# 1-Schematic_5G23new.net
KiCad netlist of a schematic drawn in EasyEDA
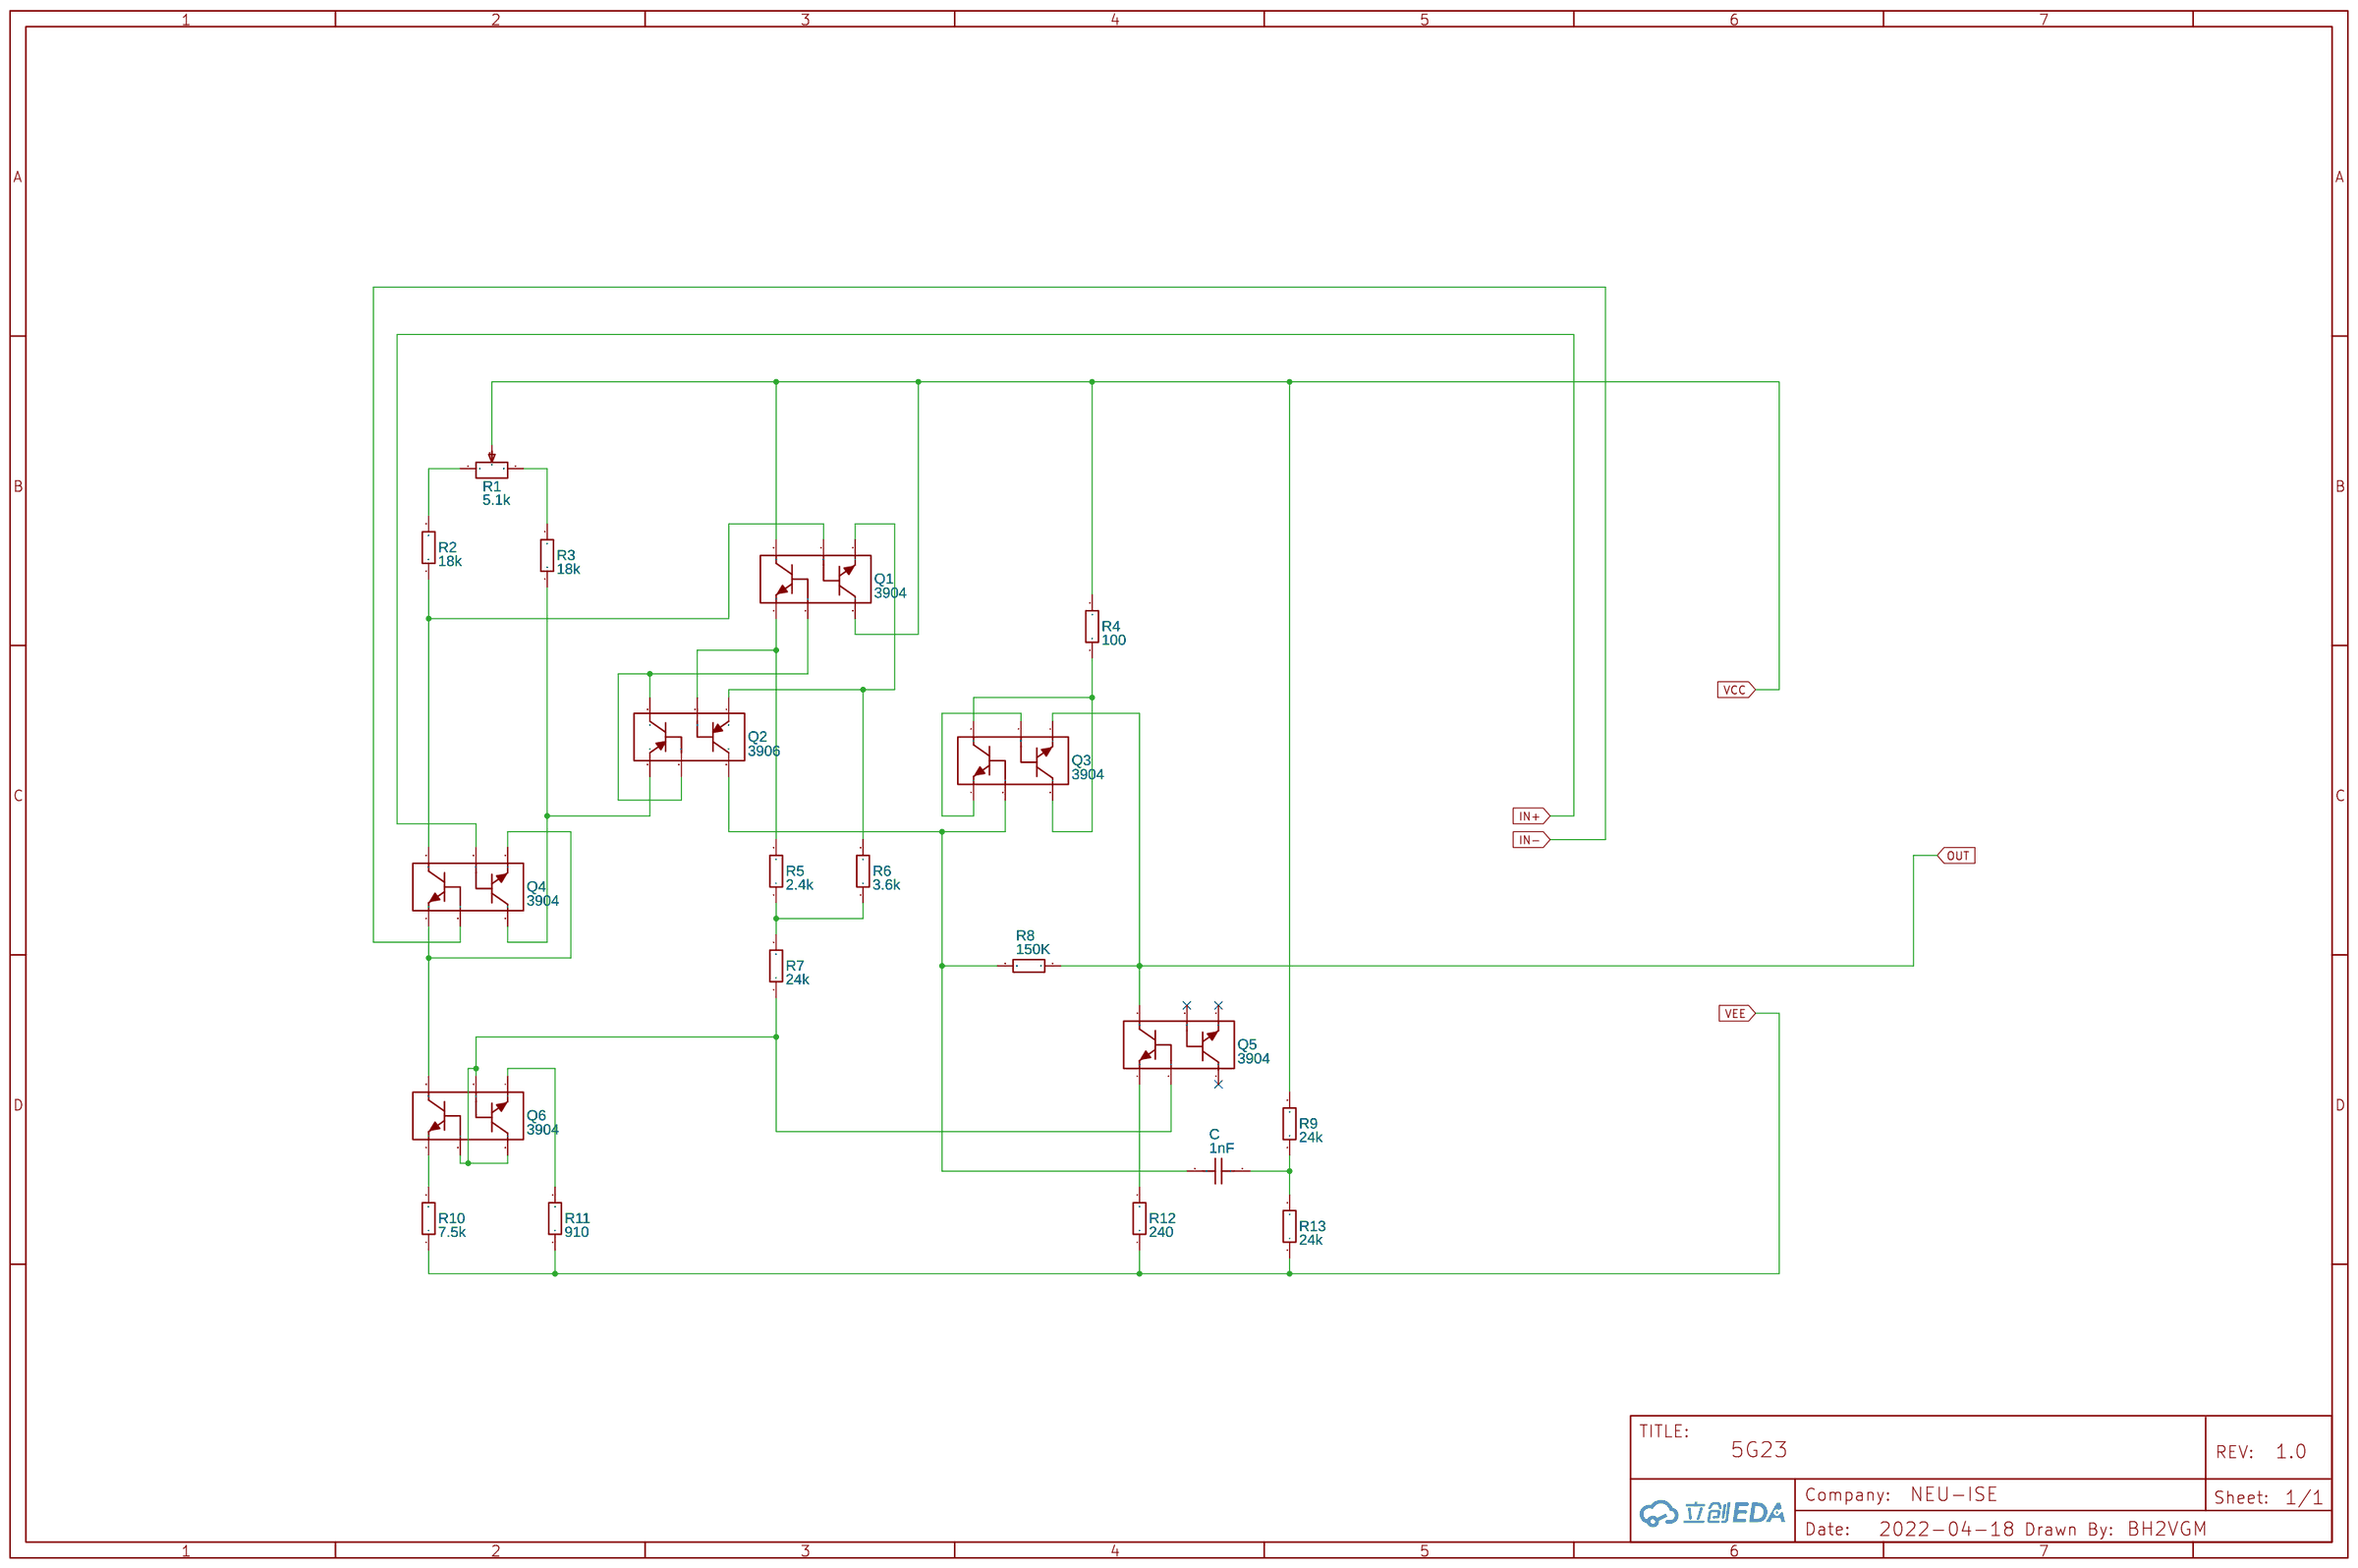
[diagram p0: 5G23]
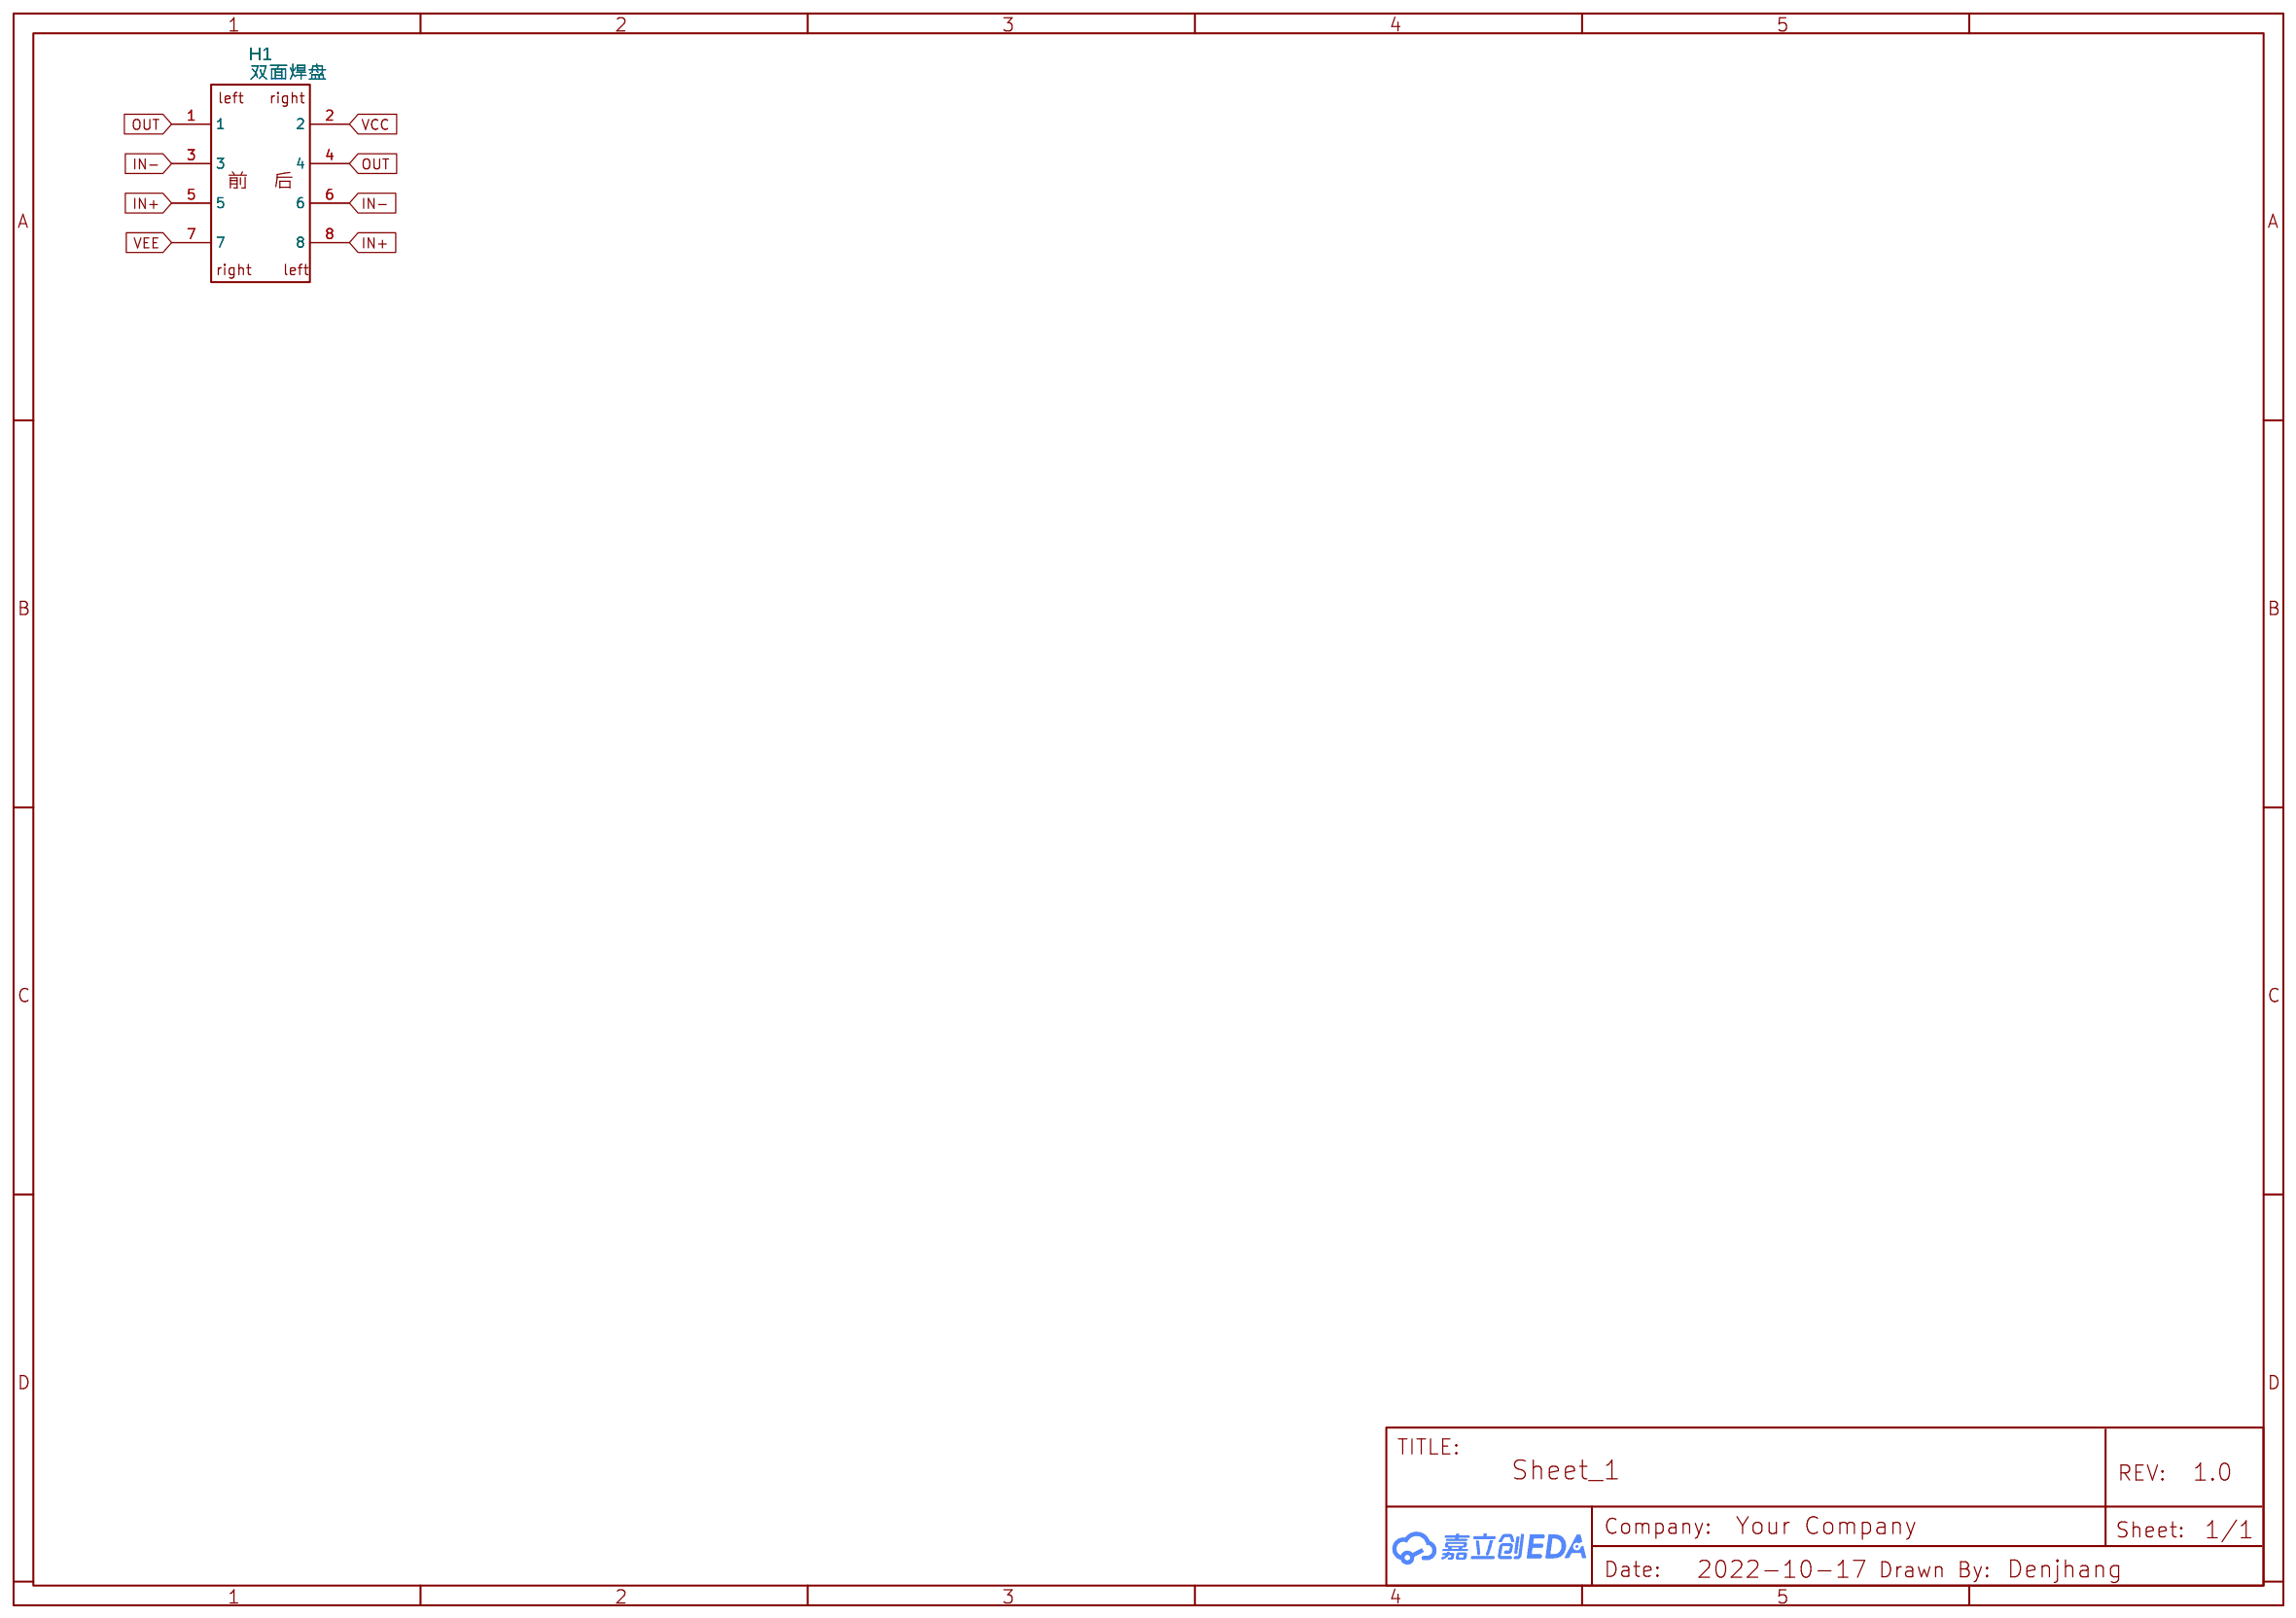
[diagram p1: CONN]

(export (version "E")
  (design (tool "Eeschema 10.0.6"))
  (components
    (comp (ref "C")
      (value "1nF")
      (fields
        (field (name "BOM_Manufacturer Part") "1nF-C0603")
        (field (name "BOM_Supplier Part") "C2940049")
      )
      (libsource (lib "") (part "1NF-C0603"))
    )
    (comp (ref "Q1")
      (value "3904")
      (fields
        (field (name "BOM_Manufacturer Part") "MMDT3904-7-F")
        (field (name "BOM_Supplier Part") "C83572")
      )
      (libsource (lib "") (part "MMDT3904"))
    )
    (comp (ref "Q2")
      (value "3906")
      (fields
        (field (name "BOM_Manufacturer Part") "MMDT3906-TP")
        (field (name "BOM_Supplier Part") "C779248")
      )
      (libsource (lib "") (part "MMDT3906"))
    )
    (comp (ref "Q3")
      (value "3904")
      (fields
        (field (name "BOM_Manufacturer Part") "MMDT3904-7-F")
        (field (name "BOM_Supplier Part") "C83572")
      )
      (libsource (lib "") (part "MMDT3904"))
    )
    (comp (ref "Q4")
      (value "3904")
      (fields
        (field (name "BOM_Manufacturer Part") "MMDT3904-7-F")
        (field (name "BOM_Supplier Part") "C83572")
      )
      (libsource (lib "") (part "MMDT3904"))
    )
    (comp (ref "Q5")
      (value "3904")
      (fields
        (field (name "BOM_Manufacturer Part") "MMDT3904-7-F")
        (field (name "BOM_Supplier Part") "C83572")
      )
      (libsource (lib "") (part "MMDT3904"))
    )
    (comp (ref "Q6")
      (value "3904")
      (fields
        (field (name "BOM_Manufacturer Part") "MMDT3904-7-F")
        (field (name "BOM_Supplier Part") "C83572")
      )
      (libsource (lib "") (part "MMDT3904"))
    )
    (comp (ref "R1")
      (value "5.1k")
      (fields
        (field (name "BOM_Manufacturer Part") "VG039NCHXTB204")
        (field (name "BOM_Supplier Part") "C128551")
      )
      (libsource (lib "") (part "VG039NCHXTB204"))
    )
    (comp (ref "R2")
      (value "18k")
      (fields (field (name "BOM_Manufacturer Part") "0805") (field (name "BOM_Supplier Part") "C9900012715"))
      (libsource (lib "") (part "0805"))
    )
    (comp (ref "R3")
      (value "18k")
      (fields (field (name "BOM_Manufacturer Part") "0805") (field (name "BOM_Supplier Part") "C9900012715"))
      (libsource (lib "") (part "0805"))
    )
    (comp (ref "R4")
      (value "100")
      (fields (field (name "BOM_Manufacturer Part") "0805") (field (name "BOM_Supplier Part") "C9900012715"))
      (libsource (lib "") (part "0805"))
    )
    (comp (ref "R5")
      (value "2.4k")
      (fields (field (name "BOM_Manufacturer Part") "0805") (field (name "BOM_Supplier Part") "C9900012715"))
      (libsource (lib "") (part "0805"))
    )
    (comp (ref "R6")
      (value "3.6k")
      (fields (field (name "BOM_Manufacturer Part") "0805") (field (name "BOM_Supplier Part") "C9900012715"))
      (libsource (lib "") (part "0805"))
    )
    (comp (ref "R7")
      (value "24k")
      (fields (field (name "BOM_Manufacturer Part") "0805") (field (name "BOM_Supplier Part") "C9900012715"))
      (libsource (lib "") (part "0805"))
    )
    (comp (ref "R8")
      (value "150K")
      (fields (field (name "BOM_Manufacturer Part") "0805") (field (name "BOM_Supplier Part") "C9900012715"))
      (libsource (lib "") (part "0805_1"))
    )
    (comp (ref "R9")
      (value "24k")
      (fields (field (name "BOM_Manufacturer Part") "0805") (field (name "BOM_Supplier Part") "C9900012715"))
      (libsource (lib "") (part "0805"))
    )
    (comp (ref "R10")
      (value "7.5k")
      (fields (field (name "BOM_Manufacturer Part") "0805") (field (name "BOM_Supplier Part") "C9900012715"))
      (libsource (lib "") (part "0805"))
    )
    (comp (ref "R11")
      (value "910")
      (fields (field (name "BOM_Manufacturer Part") "0805") (field (name "BOM_Supplier Part") "C9900012715"))
      (libsource (lib "") (part "0805"))
    )
    (comp (ref "R12")
      (value "240")
      (fields (field (name "BOM_Manufacturer Part") "0805") (field (name "BOM_Supplier Part") "C9900012715"))
      (libsource (lib "") (part "0805"))
    )
    (comp (ref "R13")
      (value "24k")
      (fields (field (name "BOM_Manufacturer Part") "0805") (field (name "BOM_Supplier Part") "C9900012715"))
      (libsource (lib "") (part "0805"))
    )
    (comp (ref "H1") (value "双面焊盘") (libsource (lib "") (part "双面焊盘")))
  )
  (nets
    (net (code "1") (name "IN+") (class "Default")
      (node (ref "H1") (pin "5") (pinfunction "5_5") (pintype "unspecified"))
      (node (ref "H1") (pin "8") (pinfunction "8_8") (pintype "unspecified"))
      (node (ref "Q4") (pin "5") (pinfunction "B_5") (pintype "unspecified"))
    )
    (net (code "2") (name "IN-") (class "Default")
      (node (ref "H1") (pin "3") (pinfunction "3_3") (pintype "unspecified"))
      (node (ref "H1") (pin "6") (pinfunction "6_6") (pintype "unspecified"))
      (node (ref "Q4") (pin "2") (pinfunction "B_2") (pintype "unspecified"))
    )
    (net (code "3") (name "Net-(C-Pad1)") (class "Default")
      (node (ref "C") (pin "1") (pinfunction "1_1") (pintype "unspecified"))
      (node (ref "Q2") (pin "3") (pinfunction "C_3") (pintype "unspecified"))
      (node (ref "Q3") (pin "2") (pinfunction "B_2") (pintype "unspecified"))
      (node (ref "R8") (pin "2") (pinfunction "2_2") (pintype "unspecified"))
    )
    (net (code "4") (name "Net-(C-Pad2)") (class "Default")
      (node (ref "C") (pin "2") (pinfunction "2_2") (pintype "unspecified"))
      (node (ref "R13") (pin "2") (pinfunction "2_2") (pintype "unspecified"))
      (node (ref "R9") (pin "1") (pinfunction "1_1") (pintype "unspecified"))
    )
    (net (code "5") (name "Net-(Q1-B-Pad2)") (class "Default")
      (node (ref "Q1") (pin "2") (pinfunction "B_2") (pintype "unspecified"))
      (node (ref "Q2") (pin "2") (pinfunction "B_2") (pintype "unspecified"))
      (node (ref "Q2") (pin "6") (pinfunction "C_6") (pintype "unspecified"))
    )
    (net (code "6") (name "Net-(Q1-B-Pad5)") (class "Default")
      (node (ref "Q1") (pin "5") (pinfunction "B_5") (pintype "unspecified"))
      (node (ref "Q4") (pin "6") (pinfunction "C_6") (pintype "unspecified"))
      (node (ref "R2") (pin "1") (pinfunction "1_1") (pintype "unspecified"))
    )
    (net (code "7") (name "Net-(Q1-E-Pad1)") (class "Default")
      (node (ref "Q1") (pin "1") (pinfunction "E_1") (pintype "unspecified"))
      (node (ref "Q2") (pin "5") (pinfunction "B_5") (pintype "unspecified"))
      (node (ref "R5") (pin "2") (pinfunction "2_2") (pintype "unspecified"))
    )
    (net (code "8") (name "Net-(Q1-E-Pad4)") (class "Default")
      (node (ref "Q1") (pin "4") (pinfunction "E_4") (pintype "unspecified"))
      (node (ref "Q2") (pin "4") (pinfunction "E_4") (pintype "unspecified"))
      (node (ref "R6") (pin "2") (pinfunction "2_2") (pintype "unspecified"))
    )
    (net (code "9") (name "Net-(Q2-E-Pad1)") (class "Default")
      (node (ref "Q2") (pin "1") (pinfunction "E_1") (pintype "unspecified"))
      (node (ref "Q4") (pin "3") (pinfunction "C_3") (pintype "unspecified"))
      (node (ref "R3") (pin "1") (pinfunction "1_1") (pintype "unspecified"))
    )
    (net (code "10") (name "Net-(Q3-B-Pad5)") (class "Default")
      (node (ref "Q3") (pin "1") (pinfunction "E_1") (pintype "unspecified"))
      (node (ref "Q3") (pin "5") (pinfunction "B_5") (pintype "unspecified"))
    )
    (net (code "11") (name "Net-(Q3-C-Pad3)") (class "Default")
      (node (ref "Q3") (pin "3") (pinfunction "C_3") (pintype "unspecified"))
      (node (ref "Q3") (pin "6") (pinfunction "C_6") (pintype "unspecified"))
      (node (ref "R4") (pin "1") (pinfunction "1_1") (pintype "unspecified"))
    )
    (net (code "12") (name "Net-(Q4-E-Pad1)") (class "Default")
      (node (ref "Q4") (pin "1") (pinfunction "E_1") (pintype "unspecified"))
      (node (ref "Q4") (pin "4") (pinfunction "E_4") (pintype "unspecified"))
      (node (ref "Q6") (pin "6") (pinfunction "C_6") (pintype "unspecified"))
    )
    (net (code "13") (name "Net-(Q5-B-Pad2)") (class "Default")
      (node (ref "Q5") (pin "2") (pinfunction "B_2") (pintype "unspecified"))
      (node (ref "Q6") (pin "2") (pinfunction "B_2") (pintype "unspecified"))
      (node (ref "Q6") (pin "3") (pinfunction "C_3") (pintype "unspecified"))
      (node (ref "Q6") (pin "5") (pinfunction "B_5") (pintype "unspecified"))
      (node (ref "R7") (pin "1") (pinfunction "1_1") (pintype "unspecified"))
    )
    (net (code "14") (name "Net-(Q5-E-Pad1)") (class "Default")
      (node (ref "Q5") (pin "1") (pinfunction "E_1") (pintype "unspecified"))
      (node (ref "R12") (pin "2") (pinfunction "2_2") (pintype "unspecified"))
    )
    (net (code "15") (name "Net-(Q6-E-Pad1)") (class "Default")
      (node (ref "Q6") (pin "1") (pinfunction "E_1") (pintype "unspecified"))
      (node (ref "R10") (pin "2") (pinfunction "2_2") (pintype "unspecified"))
    )
    (net (code "16") (name "Net-(Q6-E-Pad4)") (class "Default")
      (node (ref "Q6") (pin "4") (pinfunction "E_4") (pintype "unspecified"))
      (node (ref "R11") (pin "2") (pinfunction "2_2") (pintype "unspecified"))
    )
    (net (code "17") (name "Net-(R1-Pad1)") (class "Default")
      (node (ref "R1") (pin "1") (pinfunction "1_1") (pintype "input"))
      (node (ref "R2") (pin "2") (pinfunction "2_2") (pintype "unspecified"))
    )
    (net (code "18") (name "Net-(R1-Pad3)") (class "Default")
      (node (ref "R1") (pin "3") (pinfunction "3_3") (pintype "input"))
      (node (ref "R3") (pin "2") (pinfunction "2_2") (pintype "unspecified"))
    )
    (net (code "19") (name "Net-(R5-Pad1)") (class "Default")
      (node (ref "R5") (pin "1") (pinfunction "1_1") (pintype "unspecified"))
      (node (ref "R6") (pin "1") (pinfunction "1_1") (pintype "unspecified"))
      (node (ref "R7") (pin "2") (pinfunction "2_2") (pintype "unspecified"))
    )
    (net (code "20") (name "OUT") (class "Default")
      (node (ref "H1") (pin "1") (pinfunction "1_1") (pintype "unspecified"))
      (node (ref "H1") (pin "4") (pinfunction "4_4") (pintype "unspecified"))
      (node (ref "Q3") (pin "4") (pinfunction "E_4") (pintype "unspecified"))
      (node (ref "Q5") (pin "6") (pinfunction "C_6") (pintype "unspecified"))
      (node (ref "R8") (pin "1") (pinfunction "1_1") (pintype "unspecified"))
    )
    (net (code "21") (name "VCC") (class "Default")
      (node (ref "H1") (pin "2") (pinfunction "2_2") (pintype "unspecified"))
      (node (ref "Q1") (pin "3") (pinfunction "C_3") (pintype "unspecified"))
      (node (ref "Q1") (pin "6") (pinfunction "C_6") (pintype "unspecified"))
      (node (ref "R1") (pin "2") (pinfunction "2_2") (pintype "input"))
      (node (ref "R4") (pin "2") (pinfunction "2_2") (pintype "unspecified"))
      (node (ref "R9") (pin "2") (pinfunction "2_2") (pintype "unspecified"))
    )
    (net (code "22") (name "VEE") (class "Default")
      (node (ref "H1") (pin "7") (pinfunction "7_7") (pintype "unspecified"))
      (node (ref "R10") (pin "1") (pinfunction "1_1") (pintype "unspecified"))
      (node (ref "R11") (pin "1") (pinfunction "1_1") (pintype "unspecified"))
      (node (ref "R12") (pin "1") (pinfunction "1_1") (pintype "unspecified"))
      (node (ref "R13") (pin "1") (pinfunction "1_1") (pintype "unspecified"))
    )
    (net (code "23") (name "unconnected-(Q5-B-Pad5)") (class "Default")
      (node (ref "Q5") (pin "5") (pinfunction "B_5") (pintype "unspecified+no_connect"))
    )
    (net (code "24") (name "unconnected-(Q5-C-Pad3)") (class "Default")
      (node (ref "Q5") (pin "3") (pinfunction "C_3") (pintype "unspecified+no_connect"))
    )
    (net (code "25") (name "unconnected-(Q5-E-Pad4)") (class "Default")
      (node (ref "Q5") (pin "4") (pinfunction "E_4") (pintype "unspecified+no_connect"))
    )
  )
)
